# Dual_VCA_large_-_Rev3.net
KiCad netlist of a schematic drawn in EAGLE
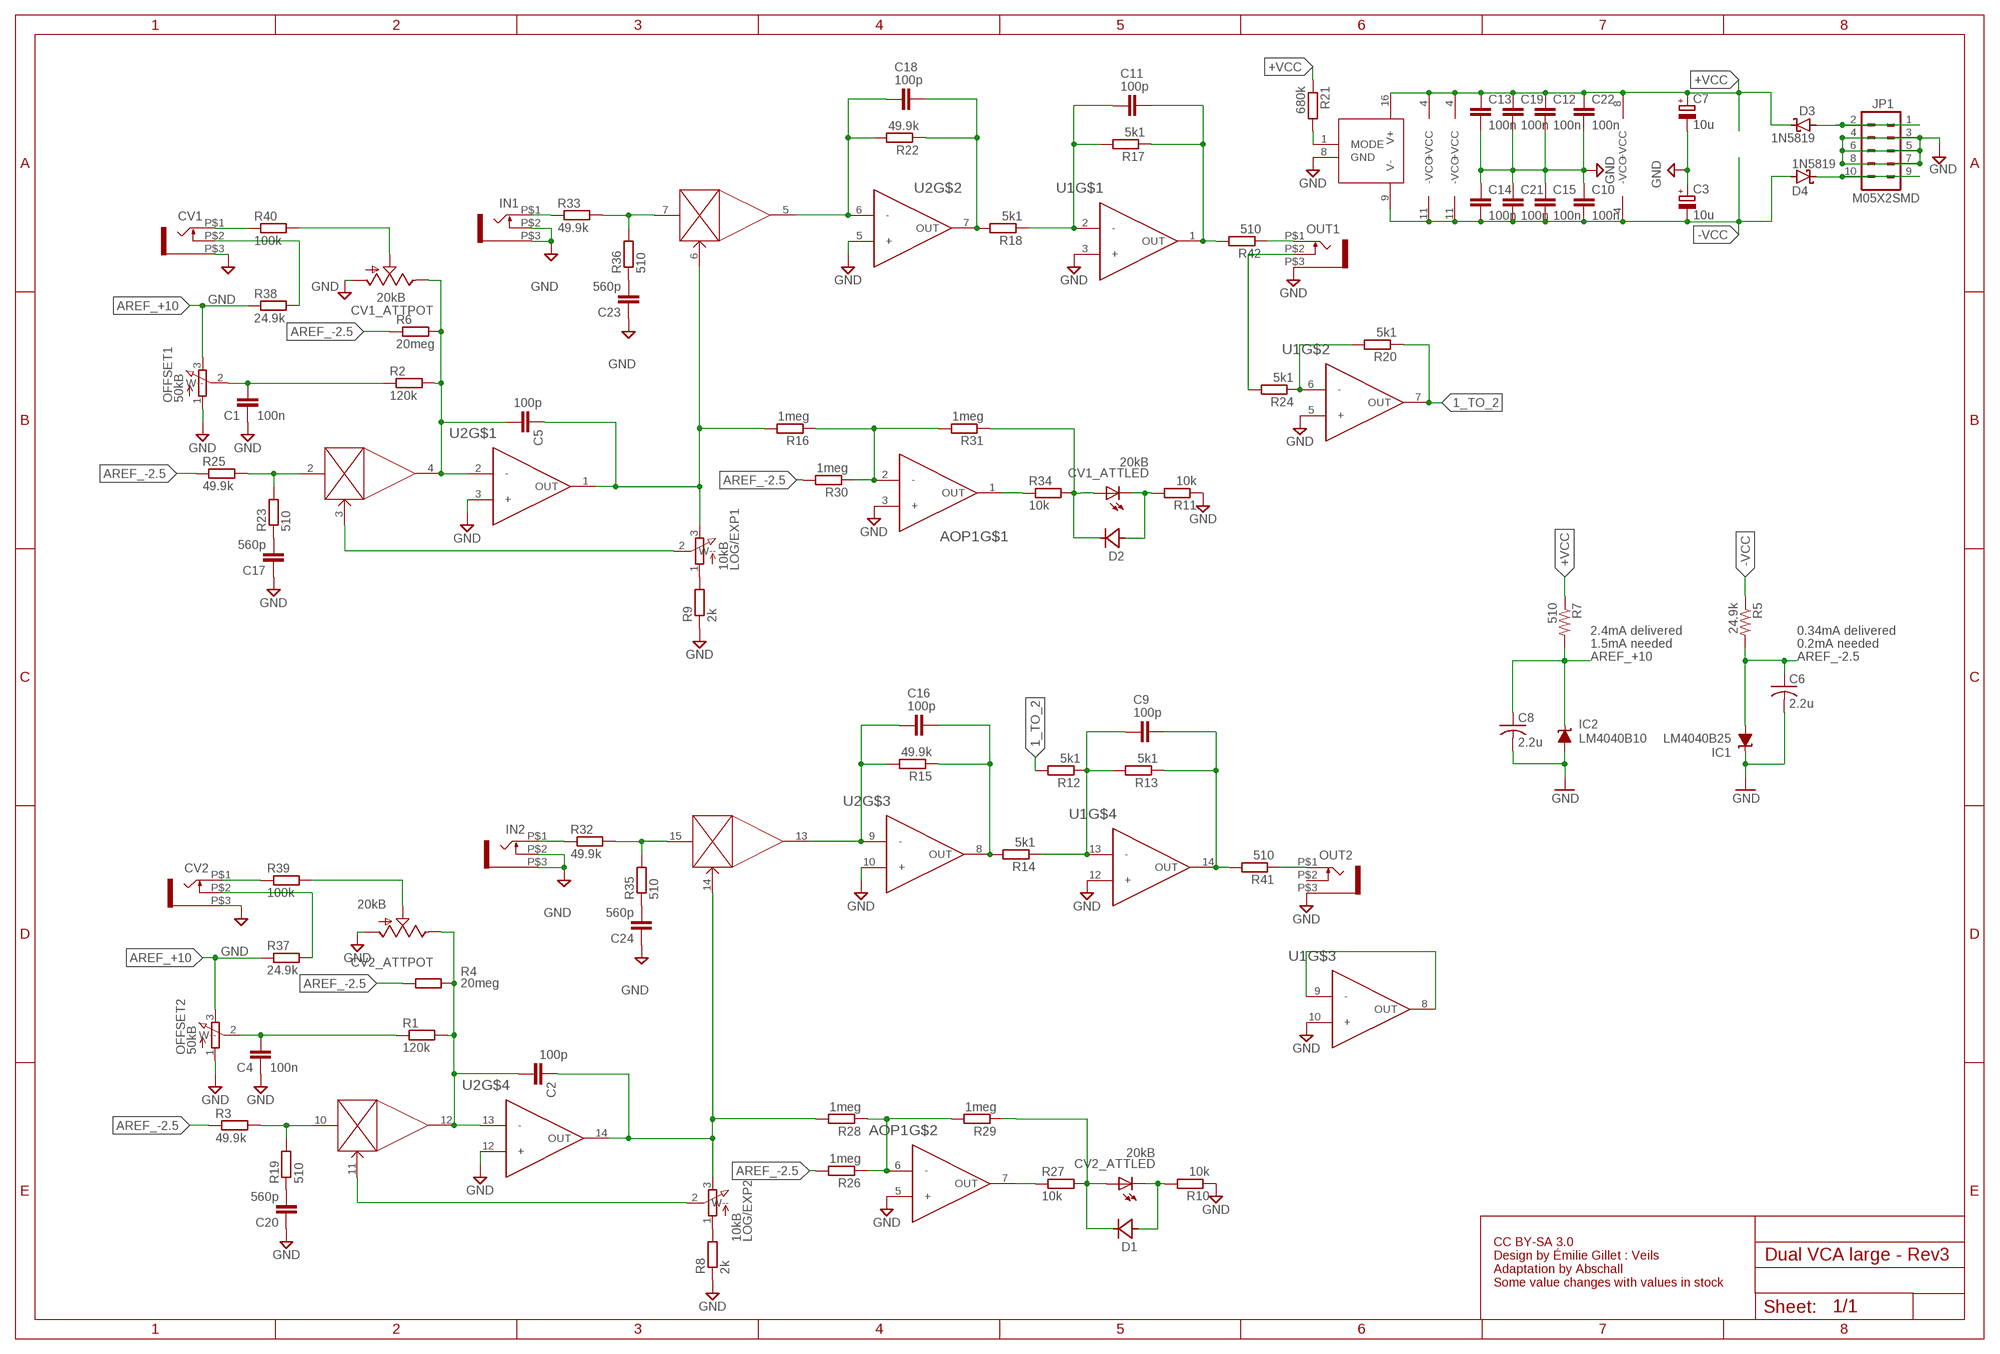
[diagram p0: schematic, sheet 1]

(export (version "E")
  (design (tool "Eeschema 10.0.6"))
  (components
    (comp (ref "AOP1")
      (value "TL072ACDR")
      (footprint "eagle-import:SOIC8")
      (libsource (lib "eagle-import") (part "TL072ACDR"))
    )
    (comp (ref "C1")
      (value "100n")
      (footprint "eagle-import:C0805K")
      (libsource (lib "eagle-import") (part "C-EUC0805K"))
    )
    (comp (ref "C2")
      (value "100p")
      (footprint "eagle-import:C0805K")
      (libsource (lib "eagle-import") (part "C-EUC0805K"))
    )
    (comp (ref "C3")
      (value "10u")
      (footprint "eagle-import:PANASONIC_B")
      (libsource (lib "eagle-import") (part "CPOL-EUB"))
    )
    (comp (ref "C4")
      (value "100n")
      (footprint "eagle-import:C0805K")
      (libsource (lib "eagle-import") (part "C-EUC0805K"))
    )
    (comp (ref "C5")
      (value "100p")
      (footprint "eagle-import:C0805K")
      (libsource (lib "eagle-import") (part "C-EUC0805K"))
    )
    (comp (ref "C6")
      (value "2.2u")
      (footprint "eagle-import:C0805")
      (libsource (lib "eagle-import") (part "C-USC0805"))
    )
    (comp (ref "C7")
      (value "10u")
      (footprint "eagle-import:PANASONIC_B")
      (libsource (lib "eagle-import") (part "CPOL-EUB"))
    )
    (comp (ref "C8")
      (value "2.2u")
      (footprint "eagle-import:C0805")
      (libsource (lib "eagle-import") (part "C-USC0805"))
    )
    (comp (ref "C9")
      (value "100p")
      (footprint "eagle-import:C0805K")
      (libsource (lib "eagle-import") (part "C-EUC0805K"))
    )
    (comp (ref "C10")
      (value "100n")
      (footprint "eagle-import:C0805K")
      (libsource (lib "eagle-import") (part "C-EUC0805K"))
    )
    (comp (ref "C11")
      (value "100p")
      (footprint "eagle-import:C0805K")
      (libsource (lib "eagle-import") (part "C-EUC0805K"))
    )
    (comp (ref "C12")
      (value "100n")
      (footprint "eagle-import:C0805K")
      (libsource (lib "eagle-import") (part "C-EUC0805K"))
    )
    (comp (ref "C13")
      (value "100n")
      (footprint "eagle-import:C0805K")
      (libsource (lib "eagle-import") (part "C-EUC0805K"))
    )
    (comp (ref "C14")
      (value "100n")
      (footprint "eagle-import:C0805K")
      (libsource (lib "eagle-import") (part "C-EUC0805K"))
    )
    (comp (ref "C15")
      (value "100n")
      (footprint "eagle-import:C0805K")
      (libsource (lib "eagle-import") (part "C-EUC0805K"))
    )
    (comp (ref "C16")
      (value "100p")
      (footprint "eagle-import:C0805K")
      (libsource (lib "eagle-import") (part "C-EUC0805K"))
    )
    (comp (ref "C17")
      (value "560p")
      (footprint "eagle-import:C0805K")
      (libsource (lib "eagle-import") (part "C-EUC0805K"))
    )
    (comp (ref "C18")
      (value "100p")
      (footprint "eagle-import:C0805K")
      (libsource (lib "eagle-import") (part "C-EUC0805K"))
    )
    (comp (ref "C19")
      (value "100n")
      (footprint "eagle-import:C0805K")
      (libsource (lib "eagle-import") (part "C-EUC0805K"))
    )
    (comp (ref "C20")
      (value "560p")
      (footprint "eagle-import:C0805K")
      (libsource (lib "eagle-import") (part "C-EUC0805K"))
    )
    (comp (ref "C21")
      (value "100n")
      (footprint "eagle-import:C0805K")
      (libsource (lib "eagle-import") (part "C-EUC0805K"))
    )
    (comp (ref "C22")
      (value "100n")
      (footprint "eagle-import:C0805K")
      (libsource (lib "eagle-import") (part "C-EUC0805K"))
    )
    (comp (ref "C23")
      (value "560p")
      (footprint "eagle-import:C0805K")
      (libsource (lib "eagle-import") (part "C-EUC0805K"))
    )
    (comp (ref "C24")
      (value "560p")
      (footprint "eagle-import:C0805K")
      (libsource (lib "eagle-import") (part "C-EUC0805K"))
    )
    (comp (ref "CV1")
      (value "WQP-PJ301M-12_JACK")
      (footprint "eagle-import:WQP-PJ301M-12_JACK")
      (libsource (lib "eagle-import") (part "WQP-PJ301M-12_JACK"))
    )
    (comp (ref "CV1_ATT")
      (value "20kB")
      (footprint "eagle-import:BOURNS_SLIDER")
      (libsource (lib "eagle-import") (part "BOURNS_SLIDER"))
    )
    (comp (ref "CV2")
      (value "WQP-PJ301M-12_JACK")
      (footprint "eagle-import:WQP-PJ301M-12_JACK")
      (libsource (lib "eagle-import") (part "WQP-PJ301M-12_JACK"))
    )
    (comp (ref "CV2_ATT")
      (value "20kB")
      (footprint "eagle-import:BOURNS_SLIDER")
      (libsource (lib "eagle-import") (part "BOURNS_SLIDER"))
    )
    (comp (ref "D1")
      (value "1N4148WX")
      (footprint "eagle-import:SOD323-W")
      (libsource (lib "eagle-import") (part "1N4148WX"))
    )
    (comp (ref "D2")
      (value "1N4148WX")
      (footprint "eagle-import:SOD323-W")
      (libsource (lib "eagle-import") (part "1N4148WX"))
    )
    (comp (ref "D3")
      (value "1N5819")
      (footprint "eagle-import:SOD123")
      (libsource (lib "eagle-import") (part "1N5819"))
    )
    (comp (ref "D4")
      (value "1N5819")
      (footprint "eagle-import:SOD123")
      (libsource (lib "eagle-import") (part "1N5819"))
    )
    (comp (ref "IC1")
      (value "LM4040B25")
      (footprint "eagle-import:DBZ_R-PDSO-G3")
      (libsource (lib "eagle-import") (part "LM4041DBZB12"))
    )
    (comp (ref "IC2")
      (value "LM4040B10")
      (footprint "eagle-import:DBZ_R-PDSO-G3")
      (libsource (lib "eagle-import") (part "LM4041DBZB12"))
    )
    (comp (ref "IN1")
      (value "WQP-PJ301M-12_JACK")
      (footprint "eagle-import:WQP-PJ301M-12_JACK")
      (libsource (lib "eagle-import") (part "WQP-PJ301M-12_JACK"))
    )
    (comp (ref "IN2")
      (value "WQP-PJ301M-12_JACK")
      (footprint "eagle-import:WQP-PJ301M-12_JACK")
      (libsource (lib "eagle-import") (part "WQP-PJ301M-12_JACK"))
    )
    (comp (ref "JP1")
      (value "M05X2SMD")
      (footprint "eagle-import:2X5-SMD")
      (libsource (lib "eagle-import") (part "M05X2SMD"))
    )
    (comp (ref "LOG/EXP1")
      (value "10kB")
      (footprint "eagle-import:ALPHA9MM-SH")
      (libsource (lib "eagle-import") (part "ALPHA9MMSMALL_HOLE"))
    )
    (comp (ref "LOG/EXP2")
      (value "10kB")
      (footprint "eagle-import:ALPHA9MM-SH")
      (libsource (lib "eagle-import") (part "ALPHA9MMSMALL_HOLE"))
    )
    (comp (ref "OFFSET1")
      (value "50kB")
      (footprint "eagle-import:ALPHA9MM-SH")
      (libsource (lib "eagle-import") (part "ALPHA9MMSMALL_HOLE"))
    )
    (comp (ref "OFFSET2")
      (value "50kB")
      (footprint "eagle-import:ALPHA9MM-SH")
      (libsource (lib "eagle-import") (part "ALPHA9MMSMALL_HOLE"))
    )
    (comp (ref "OUT1")
      (value "WQP-PJ301M-12_JACK")
      (footprint "eagle-import:WQP-PJ301M-12_JACK")
      (libsource (lib "eagle-import") (part "WQP-PJ301M-12_JACK"))
    )
    (comp (ref "OUT2")
      (value "WQP-PJ301M-12_JACK")
      (footprint "eagle-import:WQP-PJ301M-12_JACK")
      (libsource (lib "eagle-import") (part "WQP-PJ301M-12_JACK"))
    )
    (comp (ref "R1")
      (value "120k")
      (footprint "eagle-import:R0805")
      (libsource (lib "eagle-import") (part "resistor_348_R-EU_R0805"))
    )
    (comp (ref "R2")
      (value "120k")
      (footprint "eagle-import:R0805")
      (libsource (lib "eagle-import") (part "resistor_348_R-EU_R0805"))
    )
    (comp (ref "R3")
      (value "49.9k")
      (footprint "eagle-import:R0805")
      (libsource (lib "eagle-import") (part "resistor_348_R-EU_R0805"))
    )
    (comp (ref "R4")
      (value "20meg")
      (footprint "eagle-import:R0805")
      (libsource (lib "eagle-import") (part "resistor_348_R-EU_R0805"))
    )
    (comp (ref "R5")
      (value "24.9k")
      (footprint "eagle-import:R0805")
      (libsource (lib "eagle-import") (part "R-US_R0805"))
    )
    (comp (ref "R6")
      (value "20meg")
      (footprint "eagle-import:R0805")
      (libsource (lib "eagle-import") (part "resistor_348_R-EU_R0805"))
    )
    (comp (ref "R7")
      (value "510")
      (footprint "eagle-import:R0805")
      (libsource (lib "eagle-import") (part "R-US_R0805"))
    )
    (comp (ref "R8")
      (value "2k")
      (footprint "eagle-import:R0805")
      (libsource (lib "eagle-import") (part "resistor_348_R-EU_R0805"))
    )
    (comp (ref "R9")
      (value "2k")
      (footprint "eagle-import:R0805")
      (libsource (lib "eagle-import") (part "resistor_348_R-EU_R0805"))
    )
    (comp (ref "R10")
      (value "10k")
      (footprint "eagle-import:R0805")
      (libsource (lib "eagle-import") (part "resistor_348_R-EU_R0805"))
    )
    (comp (ref "R11")
      (value "10k")
      (footprint "eagle-import:R0805")
      (libsource (lib "eagle-import") (part "resistor_348_R-EU_R0805"))
    )
    (comp (ref "R12")
      (value "5k1")
      (footprint "eagle-import:R0805")
      (libsource (lib "eagle-import") (part "resistor_348_R-EU_R0805"))
    )
    (comp (ref "R13")
      (value "5k1")
      (footprint "eagle-import:R0805")
      (libsource (lib "eagle-import") (part "resistor_348_R-EU_R0805"))
    )
    (comp (ref "R14")
      (value "5k1")
      (footprint "eagle-import:R0805")
      (libsource (lib "eagle-import") (part "resistor_348_R-EU_R0805"))
    )
    (comp (ref "R15")
      (value "49.9k")
      (footprint "eagle-import:R0805")
      (libsource (lib "eagle-import") (part "resistor_348_R-EU_R0805"))
    )
    (comp (ref "R16")
      (value "1meg")
      (footprint "eagle-import:R0805")
      (libsource (lib "eagle-import") (part "resistor_348_R-EU_R0805"))
    )
    (comp (ref "R17")
      (value "5k1")
      (footprint "eagle-import:R0805")
      (libsource (lib "eagle-import") (part "resistor_348_R-EU_R0805"))
    )
    (comp (ref "R18")
      (value "5k1")
      (footprint "eagle-import:R0805")
      (libsource (lib "eagle-import") (part "resistor_348_R-EU_R0805"))
    )
    (comp (ref "R19")
      (value "510")
      (footprint "eagle-import:R0805")
      (libsource (lib "eagle-import") (part "resistor_348_R-EU_R0805"))
    )
    (comp (ref "R20")
      (value "5k1")
      (footprint "eagle-import:R0805")
      (libsource (lib "eagle-import") (part "resistor_348_R-EU_R0805"))
    )
    (comp (ref "R21")
      (value "680k")
      (footprint "eagle-import:R0805")
      (libsource (lib "eagle-import") (part "resistor_348_R-EU_R0805"))
    )
    (comp (ref "R22")
      (value "49.9k")
      (footprint "eagle-import:R0805")
      (libsource (lib "eagle-import") (part "resistor_348_R-EU_R0805"))
    )
    (comp (ref "R23")
      (value "510")
      (footprint "eagle-import:R0805")
      (libsource (lib "eagle-import") (part "resistor_348_R-EU_R0805"))
    )
    (comp (ref "R24")
      (value "5k1")
      (footprint "eagle-import:R0805")
      (libsource (lib "eagle-import") (part "resistor_348_R-EU_R0805"))
    )
    (comp (ref "R25")
      (value "49.9k")
      (footprint "eagle-import:R0805")
      (libsource (lib "eagle-import") (part "resistor_348_R-EU_R0805"))
    )
    (comp (ref "R26")
      (value "1meg")
      (footprint "eagle-import:R0805")
      (libsource (lib "eagle-import") (part "resistor_348_R-EU_R0805"))
    )
    (comp (ref "R27")
      (value "10k")
      (footprint "eagle-import:R0805")
      (libsource (lib "eagle-import") (part "resistor_348_R-EU_R0805"))
    )
    (comp (ref "R28")
      (value "1meg")
      (footprint "eagle-import:R0805")
      (libsource (lib "eagle-import") (part "resistor_348_R-EU_R0805"))
    )
    (comp (ref "R29")
      (value "1meg")
      (footprint "eagle-import:R0805")
      (libsource (lib "eagle-import") (part "resistor_348_R-EU_R0805"))
    )
    (comp (ref "R30")
      (value "1meg")
      (footprint "eagle-import:R0805")
      (libsource (lib "eagle-import") (part "resistor_348_R-EU_R0805"))
    )
    (comp (ref "R31")
      (value "1meg")
      (footprint "eagle-import:R0805")
      (libsource (lib "eagle-import") (part "resistor_348_R-EU_R0805"))
    )
    (comp (ref "R32")
      (value "49.9k")
      (footprint "eagle-import:R0805")
      (libsource (lib "eagle-import") (part "resistor_348_R-EU_R0805"))
    )
    (comp (ref "R33")
      (value "49.9k")
      (footprint "eagle-import:R0805")
      (libsource (lib "eagle-import") (part "resistor_348_R-EU_R0805"))
    )
    (comp (ref "R34")
      (value "10k")
      (footprint "eagle-import:R0805")
      (libsource (lib "eagle-import") (part "resistor_348_R-EU_R0805"))
    )
    (comp (ref "R35")
      (value "510")
      (footprint "eagle-import:R0805")
      (libsource (lib "eagle-import") (part "resistor_348_R-EU_R0805"))
    )
    (comp (ref "R36")
      (value "510")
      (footprint "eagle-import:R0805")
      (libsource (lib "eagle-import") (part "R-EU_R0805"))
    )
    (comp (ref "R37")
      (value "24.9k")
      (footprint "eagle-import:R0805")
      (libsource (lib "eagle-import") (part "resistor_348_R-EU_R0805"))
    )
    (comp (ref "R38")
      (value "24.9k")
      (footprint "eagle-import:R0805")
      (libsource (lib "eagle-import") (part "resistor_348_R-EU_R0805"))
    )
    (comp (ref "R39")
      (value "100k")
      (footprint "eagle-import:R0805")
      (libsource (lib "eagle-import") (part "resistor_348_R-EU_R0805"))
    )
    (comp (ref "R40")
      (value "100k")
      (footprint "eagle-import:R0805")
      (libsource (lib "eagle-import") (part "resistor_348_R-EU_R0805"))
    )
    (comp (ref "R41")
      (value "510")
      (footprint "eagle-import:R0805")
      (libsource (lib "eagle-import") (part "resistor_348_R-EU_R0805"))
    )
    (comp (ref "R42")
      (value "510")
      (footprint "eagle-import:R0805")
      (libsource (lib "eagle-import") (part "resistor_348_R-EU_R0805"))
    )
    (comp (ref "U1")
      (value "TL74CD")
      (footprint "eagle-import:SO14")
      (libsource (lib "eagle-import") (part "TL74CD"))
    )
    (comp (ref "U2")
      (value "TL74CD")
      (footprint "eagle-import:SO14")
      (libsource (lib "eagle-import") (part "TL74CD"))
    )
    (comp (ref "VCA1")
      (value "V2164SOIC16N")
      (footprint "eagle-import:SOIC16N")
      (libsource (lib "eagle-import") (part "V2164SOIC16N"))
    )
  )
  (nets
    (net (code "1") (name "+VCC") (class "Default")
      (node (ref "AOP1") (pin "8") (pinfunction "+VCC_8") (pintype "power_in"))
      (node (ref "C12") (pin "1") (pinfunction "1_1") (pintype "passive"))
      (node (ref "C13") (pin "1") (pinfunction "1_1") (pintype "passive"))
      (node (ref "C19") (pin "1") (pinfunction "1_1") (pintype "passive"))
      (node (ref "C22") (pin "1") (pinfunction "1_1") (pintype "passive"))
      (node (ref "C7") (pin "+") (pinfunction "+_+") (pintype "passive"))
      (node (ref "D3") (pin "C") (pinfunction "C_C") (pintype "passive"))
      (node (ref "R21") (pin "1") (pinfunction "1_1") (pintype "passive"))
      (node (ref "R7") (pin "1") (pinfunction "1_1") (pintype "passive"))
      (node (ref "U1") (pin "4") (pinfunction "+VCC_4") (pintype "power_in"))
      (node (ref "U2") (pin "4") (pinfunction "+VCC_4") (pintype "power_in"))
      (node (ref "VCA1") (pin "16") (pinfunction "V+_16") (pintype "power_in"))
    )
    (net (code "2") (name "-VCC") (class "Default")
      (node (ref "AOP1") (pin "4") (pinfunction "-VCC_4") (pintype "power_in"))
      (node (ref "C10") (pin "2") (pinfunction "2_2") (pintype "passive"))
      (node (ref "C14") (pin "2") (pinfunction "2_2") (pintype "passive"))
      (node (ref "C15") (pin "2") (pinfunction "2_2") (pintype "passive"))
      (node (ref "C21") (pin "2") (pinfunction "2_2") (pintype "passive"))
      (node (ref "C3") (pin "-") (pinfunction "-_-") (pintype "passive"))
      (node (ref "D4") (pin "A") (pinfunction "A_A") (pintype "passive"))
      (node (ref "R5") (pin "1") (pinfunction "1_1") (pintype "passive"))
      (node (ref "U1") (pin "11") (pinfunction "-VCC_11") (pintype "power_in"))
      (node (ref "U2") (pin "11") (pinfunction "-VCC_11") (pintype "power_in"))
      (node (ref "VCA1") (pin "9") (pinfunction "V-_9") (pintype "power_in"))
    )
    (net (code "3") (name "1_TO_2") (class "Default")
      (node (ref "R12") (pin "2") (pinfunction "2_2") (pintype "passive"))
      (node (ref "R20") (pin "1") (pinfunction "1_1") (pintype "passive"))
      (node (ref "U1") (pin "7") (pinfunction "OUT_7") (pintype "output"))
    )
    (net (code "4") (name "AREF_+10") (class "Default")
      (node (ref "C8") (pin "1") (pinfunction "1_1") (pintype "passive"))
      (node (ref "IC2") (pin "1") (pinfunction "C_1") (pintype "passive"))
      (node (ref "OFFSET1") (pin "3") (pinfunction "3_3") (pintype "passive"))
      (node (ref "OFFSET2") (pin "3") (pinfunction "3_3") (pintype "passive"))
      (node (ref "R37") (pin "1") (pinfunction "1_1") (pintype "passive"))
      (node (ref "R38") (pin "1") (pinfunction "1_1") (pintype "passive"))
      (node (ref "R7") (pin "2") (pinfunction "2_2") (pintype "passive"))
    )
    (net (code "5") (name "AREF_-2.5") (class "Default")
      (node (ref "C6") (pin "1") (pinfunction "1_1") (pintype "passive"))
      (node (ref "IC1") (pin "2") (pinfunction "A_2") (pintype "passive"))
      (node (ref "R25") (pin "1") (pinfunction "1_1") (pintype "passive"))
      (node (ref "R26") (pin "2") (pinfunction "2_2") (pintype "passive"))
      (node (ref "R3") (pin "1") (pinfunction "1_1") (pintype "passive"))
      (node (ref "R30") (pin "2") (pinfunction "2_2") (pintype "passive"))
      (node (ref "R4") (pin "1") (pinfunction "1_1") (pintype "passive"))
      (node (ref "R5") (pin "2") (pinfunction "2_2") (pintype "passive"))
      (node (ref "R6") (pin "1") (pinfunction "1_1") (pintype "passive"))
    )
    (net (code "6") (name "GND") (class "Default")
      (node (ref "AOP1") (pin "3") (pinfunction "+_3") (pintype "input"))
      (node (ref "AOP1") (pin "5") (pinfunction "+_5") (pintype "input"))
      (node (ref "C1") (pin "1") (pinfunction "1_1") (pintype "passive"))
      (node (ref "C10") (pin "1") (pinfunction "1_1") (pintype "passive"))
      (node (ref "C12") (pin "2") (pinfunction "2_2") (pintype "passive"))
      (node (ref "C13") (pin "2") (pinfunction "2_2") (pintype "passive"))
      (node (ref "C14") (pin "1") (pinfunction "1_1") (pintype "passive"))
      (node (ref "C15") (pin "1") (pinfunction "1_1") (pintype "passive"))
      (node (ref "C17") (pin "1") (pinfunction "1_1") (pintype "passive"))
      (node (ref "C19") (pin "2") (pinfunction "2_2") (pintype "passive"))
      (node (ref "C20") (pin "1") (pinfunction "1_1") (pintype "passive"))
      (node (ref "C21") (pin "1") (pinfunction "1_1") (pintype "passive"))
      (node (ref "C22") (pin "2") (pinfunction "2_2") (pintype "passive"))
      (node (ref "C23") (pin "1") (pinfunction "1_1") (pintype "passive"))
      (node (ref "C24") (pin "1") (pinfunction "1_1") (pintype "passive"))
      (node (ref "C3") (pin "+") (pinfunction "+_+") (pintype "passive"))
      (node (ref "C4") (pin "1") (pinfunction "1_1") (pintype "passive"))
      (node (ref "C6") (pin "2") (pinfunction "2_2") (pintype "passive"))
      (node (ref "C7") (pin "-") (pinfunction "-_-") (pintype "passive"))
      (node (ref "C8") (pin "2") (pinfunction "2_2") (pintype "passive"))
      (node (ref "CV1") (pin "P$3") (pinfunction "1_P$3") (pintype "passive"))
      (node (ref "CV1_ATT") (pin "1") (pinfunction "A_1") (pintype "passive"))
      (node (ref "CV2") (pin "P$3") (pinfunction "1_P$3") (pintype "passive"))
      (node (ref "CV2_ATT") (pin "1") (pinfunction "A_1") (pintype "passive"))
      (node (ref "IC1") (pin "1") (pinfunction "C_1") (pintype "passive"))
      (node (ref "IC2") (pin "2") (pinfunction "A_2") (pintype "passive"))
      (node (ref "IN1") (pin "P$2") (pinfunction "3_P$2") (pintype "passive"))
      (node (ref "IN1") (pin "P$3") (pinfunction "1_P$3") (pintype "passive"))
      (node (ref "IN2") (pin "P$2") (pinfunction "3_P$2") (pintype "passive"))
      (node (ref "IN2") (pin "P$3") (pinfunction "1_P$3") (pintype "passive"))
      (node (ref "JP1") (pin "3") (pinfunction "3_3") (pintype "passive"))
      (node (ref "JP1") (pin "4") (pinfunction "4_4") (pintype "passive"))
      (node (ref "JP1") (pin "5") (pinfunction "5_5") (pintype "passive"))
      (node (ref "JP1") (pin "6") (pinfunction "6_6") (pintype "passive"))
      (node (ref "JP1") (pin "7") (pinfunction "7_7") (pintype "passive"))
      (node (ref "JP1") (pin "8") (pinfunction "8_8") (pintype "passive"))
      (node (ref "OFFSET1") (pin "1") (pinfunction "1_1") (pintype "passive"))
      (node (ref "OFFSET2") (pin "1") (pinfunction "1_1") (pintype "passive"))
      (node (ref "OUT1") (pin "P$3") (pinfunction "1_P$3") (pintype "passive"))
      (node (ref "OUT2") (pin "P$3") (pinfunction "1_P$3") (pintype "passive"))
      (node (ref "R10") (pin "1") (pinfunction "1_1") (pintype "passive"))
      (node (ref "R11") (pin "1") (pinfunction "1_1") (pintype "passive"))
      (node (ref "R8") (pin "1") (pinfunction "1_1") (pintype "passive"))
      (node (ref "R9") (pin "1") (pinfunction "1_1") (pintype "passive"))
      (node (ref "U1") (pin "10") (pinfunction "+_10") (pintype "input"))
      (node (ref "U1") (pin "12") (pinfunction "+_12") (pintype "input"))
      (node (ref "U1") (pin "3") (pinfunction "+_3") (pintype "input"))
      (node (ref "U1") (pin "5") (pinfunction "+_5") (pintype "input"))
      (node (ref "U2") (pin "10") (pinfunction "+_10") (pintype "input"))
      (node (ref "U2") (pin "12") (pinfunction "+_12") (pintype "input"))
      (node (ref "U2") (pin "3") (pinfunction "+_3") (pintype "input"))
      (node (ref "U2") (pin "5") (pinfunction "+_5") (pintype "input"))
      (node (ref "VCA1") (pin "8") (pinfunction "GND_8") (pintype "bidirectional"))
    )
    (net (code "7") (name "Net-(AOP1A--)") (class "Default")
      (node (ref "AOP1") (pin "2") (pinfunction "-_2") (pintype "input"))
      (node (ref "R16") (pin "1") (pinfunction "1_1") (pintype "passive"))
      (node (ref "R30") (pin "1") (pinfunction "1_1") (pintype "passive"))
      (node (ref "R31") (pin "2") (pinfunction "2_2") (pintype "passive"))
    )
    (net (code "8") (name "Net-(AOP1A-OUT)") (class "Default")
      (node (ref "AOP1") (pin "1") (pinfunction "OUT_1") (pintype "output"))
      (node (ref "R34") (pin "1") (pinfunction "1_1") (pintype "passive"))
    )
    (net (code "9") (name "Net-(AOP1B--)") (class "Default")
      (node (ref "AOP1") (pin "6") (pinfunction "-_6") (pintype "input"))
      (node (ref "R26") (pin "1") (pinfunction "1_1") (pintype "passive"))
      (node (ref "R28") (pin "1") (pinfunction "1_1") (pintype "passive"))
      (node (ref "R29") (pin "2") (pinfunction "2_2") (pintype "passive"))
    )
    (net (code "10") (name "Net-(AOP1B-OUT)") (class "Default")
      (node (ref "AOP1") (pin "7") (pinfunction "OUT_7") (pintype "output"))
      (node (ref "R27") (pin "1") (pinfunction "1_1") (pintype "passive"))
    )
    (net (code "11") (name "Net-(C17-Pad2)") (class "Default")
      (node (ref "C17") (pin "2") (pinfunction "2_2") (pintype "passive"))
      (node (ref "R23") (pin "1") (pinfunction "1_1") (pintype "passive"))
    )
    (net (code "12") (name "Net-(C20-Pad2)") (class "Default")
      (node (ref "C20") (pin "2") (pinfunction "2_2") (pintype "passive"))
      (node (ref "R19") (pin "1") (pinfunction "1_1") (pintype "passive"))
    )
    (net (code "13") (name "Net-(C23-Pad2)") (class "Default")
      (node (ref "C23") (pin "2") (pinfunction "2_2") (pintype "passive"))
      (node (ref "R36") (pin "1") (pinfunction "1_1") (pintype "passive"))
    )
    (net (code "14") (name "Net-(C24-Pad2)") (class "Default")
      (node (ref "C24") (pin "2") (pinfunction "2_2") (pintype "passive"))
      (node (ref "R35") (pin "1") (pinfunction "1_1") (pintype "passive"))
    )
    (net (code "15") (name "Net-(CV1-2)") (class "Default")
      (node (ref "CV1") (pin "P$1") (pinfunction "2_P$1") (pintype "passive"))
      (node (ref "R40") (pin "1") (pinfunction "1_1") (pintype "passive"))
    )
    (net (code "16") (name "Net-(CV1-3)") (class "Default")
      (node (ref "CV1") (pin "P$2") (pinfunction "3_P$2") (pintype "passive"))
      (node (ref "R38") (pin "2") (pinfunction "2_2") (pintype "passive"))
    )
    (net (code "17") (name "Net-(CV1_ATTA-A)") (class "Default")
      (node (ref "CV1_ATT") (pin "B") (pinfunction "A_B") (pintype "passive"))
      (node (ref "D2") (pin "C") (pinfunction "C_C") (pintype "passive"))
      (node (ref "R31") (pin "1") (pinfunction "1_1") (pintype "passive"))
      (node (ref "R34") (pin "2") (pinfunction "2_2") (pintype "passive"))
    )
    (net (code "18") (name "Net-(CV1_ATTA-C)") (class "Default")
      (node (ref "CV1_ATT") (pin "E") (pinfunction "C_E") (pintype "passive"))
      (node (ref "D2") (pin "A") (pinfunction "A_A") (pintype "passive"))
      (node (ref "R11") (pin "2") (pinfunction "2_2") (pintype "passive"))
    )
    (net (code "19") (name "Net-(CV1_ATTB-E)") (class "Default")
      (node (ref "C5") (pin "2") (pinfunction "2_2") (pintype "passive"))
      (node (ref "CV1_ATT") (pin "3") (pinfunction "E_3") (pintype "passive"))
      (node (ref "R2") (pin "2") (pinfunction "2_2") (pintype "passive"))
      (node (ref "R6") (pin "2") (pinfunction "2_2") (pintype "passive"))
      (node (ref "U2") (pin "2") (pinfunction "-_2") (pintype "input"))
      (node (ref "VCA1") (pin "4") (pinfunction "OUT_4") (pintype "output"))
    )
    (net (code "20") (name "Net-(CV1_ATTB-S)") (class "Default")
      (node (ref "CV1_ATT") (pin "2") (pinfunction "S_2") (pintype "passive"))
      (node (ref "R40") (pin "2") (pinfunction "2_2") (pintype "passive"))
    )
    (net (code "21") (name "Net-(CV2-2)") (class "Default")
      (node (ref "CV2") (pin "P$1") (pinfunction "2_P$1") (pintype "passive"))
      (node (ref "R39") (pin "1") (pinfunction "1_1") (pintype "passive"))
    )
    (net (code "22") (name "Net-(CV2-3)") (class "Default")
      (node (ref "CV2") (pin "P$2") (pinfunction "3_P$2") (pintype "passive"))
      (node (ref "R37") (pin "2") (pinfunction "2_2") (pintype "passive"))
    )
    (net (code "23") (name "Net-(CV2_ATTA-A)") (class "Default")
      (node (ref "CV2_ATT") (pin "B") (pinfunction "A_B") (pintype "passive"))
      (node (ref "D1") (pin "C") (pinfunction "C_C") (pintype "passive"))
      (node (ref "R27") (pin "2") (pinfunction "2_2") (pintype "passive"))
      (node (ref "R29") (pin "1") (pinfunction "1_1") (pintype "passive"))
    )
    (net (code "24") (name "Net-(CV2_ATTA-C)") (class "Default")
      (node (ref "CV2_ATT") (pin "E") (pinfunction "C_E") (pintype "passive"))
      (node (ref "D1") (pin "A") (pinfunction "A_A") (pintype "passive"))
      (node (ref "R10") (pin "2") (pinfunction "2_2") (pintype "passive"))
    )
    (net (code "25") (name "Net-(CV2_ATTB-E)") (class "Default")
      (node (ref "C2") (pin "2") (pinfunction "2_2") (pintype "passive"))
      (node (ref "CV2_ATT") (pin "3") (pinfunction "E_3") (pintype "passive"))
      (node (ref "R1") (pin "2") (pinfunction "2_2") (pintype "passive"))
      (node (ref "R4") (pin "2") (pinfunction "2_2") (pintype "passive"))
      (node (ref "U2") (pin "13") (pinfunction "-_13") (pintype "input"))
      (node (ref "VCA1") (pin "12") (pinfunction "OUT_12") (pintype "output"))
    )
    (net (code "26") (name "Net-(CV2_ATTB-S)") (class "Default")
      (node (ref "CV2_ATT") (pin "2") (pinfunction "S_2") (pintype "passive"))
      (node (ref "R39") (pin "2") (pinfunction "2_2") (pintype "passive"))
    )
    (net (code "27") (name "Net-(D3-PadA)") (class "Default")
      (node (ref "D3") (pin "A") (pinfunction "A_A") (pintype "passive"))
      (node (ref "JP1") (pin "1") (pinfunction "1_1") (pintype "passive"))
      (node (ref "JP1") (pin "2") (pinfunction "2_2") (pintype "passive"))
    )
    (net (code "28") (name "Net-(D4-PadC)") (class "Default")
      (node (ref "D4") (pin "C") (pinfunction "C_C") (pintype "passive"))
      (node (ref "JP1") (pin "10") (pinfunction "10_10") (pintype "passive"))
      (node (ref "JP1") (pin "9") (pinfunction "9_9") (pintype "passive"))
    )
    (net (code "29") (name "Net-(IN1-2)") (class "Default")
      (node (ref "IN1") (pin "P$1") (pinfunction "2_P$1") (pintype "passive"))
      (node (ref "R33") (pin "1") (pinfunction "1_1") (pintype "passive"))
    )
    (net (code "30") (name "Net-(IN2-2)") (class "Default")
      (node (ref "IN2") (pin "P$1") (pinfunction "2_P$1") (pintype "passive"))
      (node (ref "R32") (pin "1") (pinfunction "1_1") (pintype "passive"))
    )
    (net (code "31") (name "Net-(LOG/EXP1-Pad1)") (class "Default")
      (node (ref "LOG/EXP1") (pin "1") (pinfunction "1_1") (pintype "passive"))
      (node (ref "R9") (pin "2") (pinfunction "2_2") (pintype "passive"))
    )
    (net (code "32") (name "Net-(LOG/EXP1-W--)") (class "Default")
      (node (ref "LOG/EXP1") (pin "2") (pinfunction "W--_2") (pintype "passive"))
      (node (ref "VCA1") (pin "3") (pinfunction "CV_3") (pintype "input"))
    )
    (net (code "33") (name "Net-(LOG/EXP2-Pad1)") (class "Default")
      (node (ref "LOG/EXP2") (pin "1") (pinfunction "1_1") (pintype "passive"))
      (node (ref "R8") (pin "2") (pinfunction "2_2") (pintype "passive"))
    )
    (net (code "34") (name "Net-(LOG/EXP2-W--)") (class "Default")
      (node (ref "LOG/EXP2") (pin "2") (pinfunction "W--_2") (pintype "passive"))
      (node (ref "VCA1") (pin "11") (pinfunction "CV_11") (pintype "input"))
    )
    (net (code "35") (name "Net-(OFFSET1-W--)") (class "Default")
      (node (ref "C1") (pin "2") (pinfunction "2_2") (pintype "passive"))
      (node (ref "OFFSET1") (pin "2") (pinfunction "W--_2") (pintype "passive"))
      (node (ref "R2") (pin "1") (pinfunction "1_1") (pintype "passive"))
    )
    (net (code "36") (name "Net-(OFFSET2-W--)") (class "Default")
      (node (ref "C4") (pin "2") (pinfunction "2_2") (pintype "passive"))
      (node (ref "OFFSET2") (pin "2") (pinfunction "W--_2") (pintype "passive"))
      (node (ref "R1") (pin "1") (pinfunction "1_1") (pintype "passive"))
    )
    (net (code "37") (name "Net-(OUT1-2)") (class "Default")
      (node (ref "OUT1") (pin "P$1") (pinfunction "2_P$1") (pintype "passive"))
      (node (ref "R42") (pin "1") (pinfunction "1_1") (pintype "passive"))
    )
    (net (code "38") (name "Net-(OUT1-3)") (class "Default")
      (node (ref "OUT1") (pin "P$2") (pinfunction "3_P$2") (pintype "passive"))
      (node (ref "R24") (pin "2") (pinfunction "2_2") (pintype "passive"))
    )
    (net (code "39") (name "Net-(OUT2-2)") (class "Default")
      (node (ref "OUT2") (pin "P$1") (pinfunction "2_P$1") (pintype "passive"))
      (node (ref "R41") (pin "1") (pinfunction "1_1") (pintype "passive"))
    )
    (net (code "40") (name "Net-(U1A--)") (class "Default")
      (node (ref "C11") (pin "2") (pinfunction "2_2") (pintype "passive"))
      (node (ref "R17") (pin "2") (pinfunction "2_2") (pintype "passive"))
      (node (ref "R18") (pin "1") (pinfunction "1_1") (pintype "passive"))
      (node (ref "U1") (pin "2") (pinfunction "-_2") (pintype "input"))
    )
    (net (code "41") (name "Net-(U1A-OUT)") (class "Default")
      (node (ref "C11") (pin "1") (pinfunction "1_1") (pintype "passive"))
      (node (ref "R17") (pin "1") (pinfunction "1_1") (pintype "passive"))
      (node (ref "R42") (pin "2") (pinfunction "2_2") (pintype "passive"))
      (node (ref "U1") (pin "1") (pinfunction "OUT_1") (pintype "output"))
    )
    (net (code "42") (name "Net-(U1B--)") (class "Default")
      (node (ref "R20") (pin "2") (pinfunction "2_2") (pintype "passive"))
      (node (ref "R24") (pin "1") (pinfunction "1_1") (pintype "passive"))
      (node (ref "U1") (pin "6") (pinfunction "-_6") (pintype "input"))
    )
    (net (code "43") (name "Net-(U1C--)") (class "Default")
      (node (ref "U1") (pin "8") (pinfunction "OUT_8") (pintype "output"))
      (node (ref "U1") (pin "9") (pinfunction "-_9") (pintype "input"))
    )
    (net (code "44") (name "Net-(U1D--)") (class "Default")
      (node (ref "C9") (pin "2") (pinfunction "2_2") (pintype "passive"))
      (node (ref "R12") (pin "1") (pinfunction "1_1") (pintype "passive"))
      (node (ref "R13") (pin "2") (pinfunction "2_2") (pintype "passive"))
      (node (ref "R14") (pin "1") (pinfunction "1_1") (pintype "passive"))
      (node (ref "U1") (pin "13") (pinfunction "-_13") (pintype "input"))
    )
    (net (code "45") (name "Net-(U1D-OUT)") (class "Default")
      (node (ref "C9") (pin "1") (pinfunction "1_1") (pintype "passive"))
      (node (ref "R13") (pin "1") (pinfunction "1_1") (pintype "passive"))
      (node (ref "R41") (pin "2") (pinfunction "2_2") (pintype "passive"))
      (node (ref "U1") (pin "14") (pinfunction "OUT_14") (pintype "output"))
    )
    (net (code "46") (name "Net-(U2A-OUT)") (class "Default")
      (node (ref "C5") (pin "1") (pinfunction "1_1") (pintype "passive"))
      (node (ref "LOG/EXP1") (pin "3") (pinfunction "3_3") (pintype "passive"))
      (node (ref "R16") (pin "2") (pinfunction "2_2") (pintype "passive"))
      (node (ref "U2") (pin "1") (pinfunction "OUT_1") (pintype "output"))
      (node (ref "VCA1") (pin "6") (pinfunction "CV_6") (pintype "input"))
    )
    (net (code "47") (name "Net-(U2B--)") (class "Default")
      (node (ref "C18") (pin "2") (pinfunction "2_2") (pintype "passive"))
      (node (ref "R22") (pin "2") (pinfunction "2_2") (pintype "passive"))
      (node (ref "U2") (pin "6") (pinfunction "-_6") (pintype "input"))
      (node (ref "VCA1") (pin "5") (pinfunction "OUT_5") (pintype "output"))
    )
    (net (code "48") (name "Net-(U2B-OUT)") (class "Default")
      (node (ref "C18") (pin "1") (pinfunction "1_1") (pintype "passive"))
      (node (ref "R18") (pin "2") (pinfunction "2_2") (pintype "passive"))
      (node (ref "R22") (pin "1") (pinfunction "1_1") (pintype "passive"))
      (node (ref "U2") (pin "7") (pinfunction "OUT_7") (pintype "output"))
    )
    (net (code "49") (name "Net-(U2C--)") (class "Default")
      (node (ref "C16") (pin "2") (pinfunction "2_2") (pintype "passive"))
      (node (ref "R15") (pin "2") (pinfunction "2_2") (pintype "passive"))
      (node (ref "U2") (pin "9") (pinfunction "-_9") (pintype "input"))
      (node (ref "VCA1") (pin "13") (pinfunction "OUT_13") (pintype "output"))
    )
    (net (code "50") (name "Net-(U2C-OUT)") (class "Default")
      (node (ref "C16") (pin "1") (pinfunction "1_1") (pintype "passive"))
      (node (ref "R14") (pin "2") (pinfunction "2_2") (pintype "passive"))
      (node (ref "R15") (pin "1") (pinfunction "1_1") (pintype "passive"))
      (node (ref "U2") (pin "8") (pinfunction "OUT_8") (pintype "output"))
    )
    (net (code "51") (name "Net-(U2D-OUT)") (class "Default")
      (node (ref "C2") (pin "1") (pinfunction "1_1") (pintype "passive"))
      (node (ref "LOG/EXP2") (pin "3") (pinfunction "3_3") (pintype "passive"))
      (node (ref "R28") (pin "2") (pinfunction "2_2") (pintype "passive"))
      (node (ref "U2") (pin "14") (pinfunction "OUT_14") (pintype "output"))
      (node (ref "VCA1") (pin "14") (pinfunction "CV_14") (pintype "input"))
    )
    (net (code "52") (name "Net-(VCA1A-IN)") (class "Default")
      (node (ref "R23") (pin "2") (pinfunction "2_2") (pintype "passive"))
      (node (ref "R25") (pin "2") (pinfunction "2_2") (pintype "passive"))
      (node (ref "VCA1") (pin "2") (pinfunction "IN_2") (pintype "input"))
    )
    (net (code "53") (name "Net-(VCA1B-IN)") (class "Default")
      (node (ref "R33") (pin "2") (pinfunction "2_2") (pintype "passive"))
      (node (ref "R36") (pin "2") (pinfunction "2_2") (pintype "passive"))
      (node (ref "VCA1") (pin "7") (pinfunction "IN_7") (pintype "input"))
    )
    (net (code "54") (name "Net-(VCA1C-IN)") (class "Default")
      (node (ref "R19") (pin "2") (pinfunction "2_2") (pintype "passive"))
      (node (ref "R3") (pin "2") (pinfunction "2_2") (pintype "passive"))
      (node (ref "VCA1") (pin "10") (pinfunction "IN_10") (pintype "input"))
    )
    (net (code "55") (name "Net-(VCA1D-IN)") (class "Default")
      (node (ref "R32") (pin "2") (pinfunction "2_2") (pintype "passive"))
      (node (ref "R35") (pin "2") (pinfunction "2_2") (pintype "passive"))
      (node (ref "VCA1") (pin "15") (pinfunction "IN_15") (pintype "input"))
    )
    (net (code "56") (name "Net-(VCA1E-MODE)") (class "Default")
      (node (ref "R21") (pin "2") (pinfunction "2_2") (pintype "passive"))
      (node (ref "VCA1") (pin "1") (pinfunction "MODE_1") (pintype "bidirectional"))
    )
    (net (code "57") (name "unconnected-(OUT2-3-PadP$2)") (class "Default")
      (node (ref "OUT2") (pin "P$2") (pinfunction "3_P$2") (pintype "passive"))
    )
  )
)
